# GyroAccelHeaders.net
KiCad netlist of a schematic drawn in Altium Designer
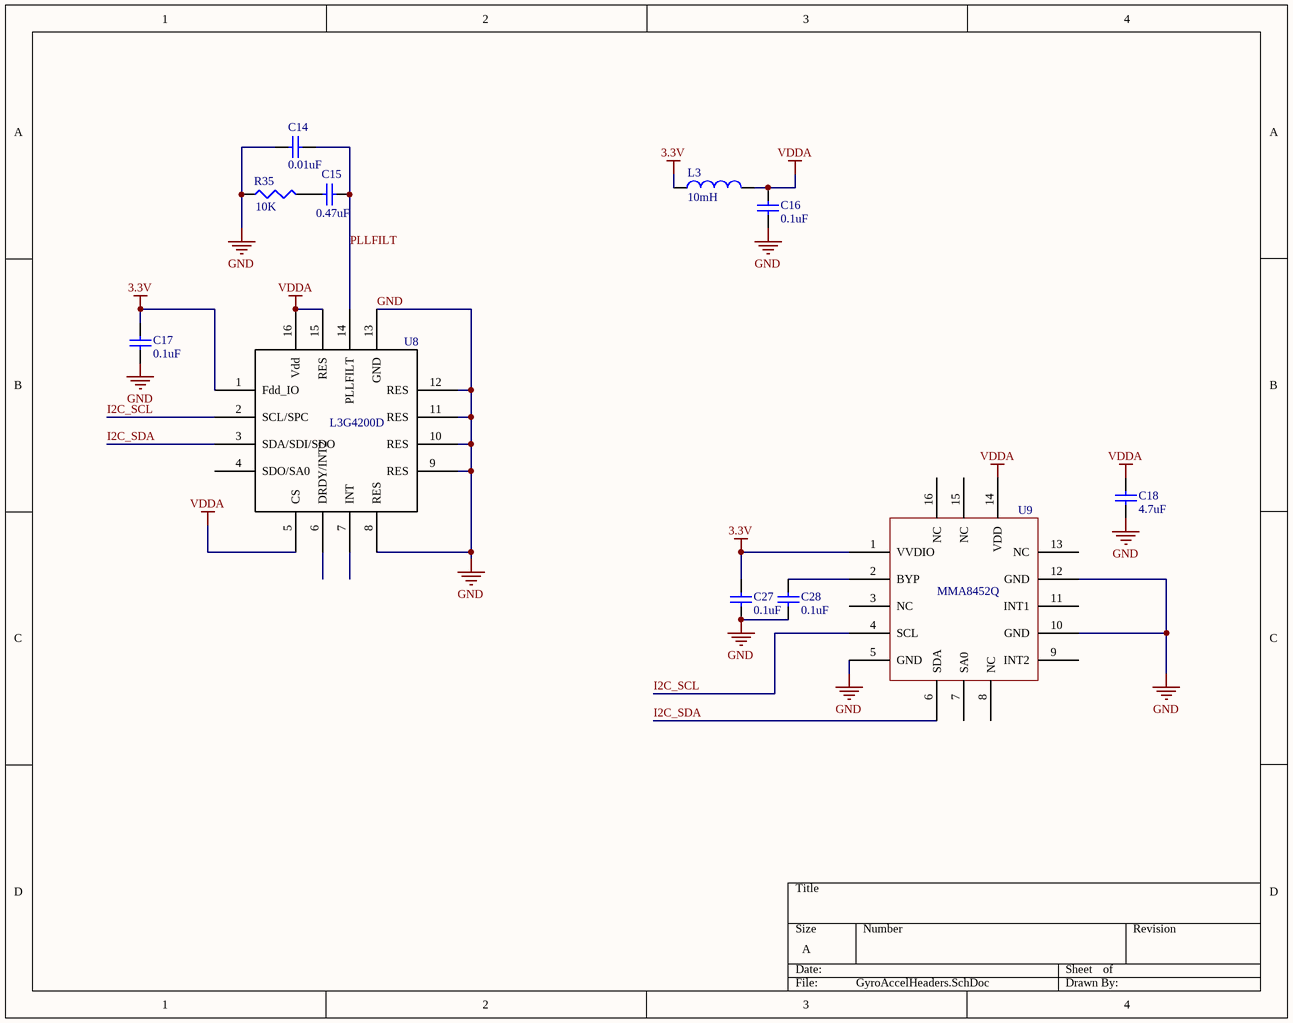
[diagram p0: GyroAccelHeaders.SchDoc]

(export (version "E")
  (design (tool "Eeschema 10.0.6"))
  (components
    (comp (ref "C14")
      (value "0.01uF")
      (footprint "CAPC1005L")
      (description "Capacitor (Semiconductor SIM Model)")
      (fields (field (name "Comment") "Cap Semi") (field (name "PUBLISHER") "Altium Limited"))
      (libsource (lib "Miscellaneous Devices") (part "Cap Semi"))
    )
    (comp (ref "C15")
      (value "0.47uF")
      (footprint "CAPC1005L")
      (description "Capacitor (Semiconductor SIM Model)")
      (fields (field (name "Comment") "Cap Semi") (field (name "PUBLISHER") "Altium Limited"))
      (libsource (lib "Miscellaneous Devices") (part "Cap Semi"))
    )
    (comp (ref "C16")
      (value "0.1uF")
      (footprint "CAPC1005L")
      (description "Capacitor (Semiconductor SIM Model)")
      (fields (field (name "Comment") "Cap Semi") (field (name "PUBLISHER") "Altium Limited"))
      (libsource (lib "Miscellaneous Devices") (part "Cap Semi"))
    )
    (comp (ref "C17")
      (value "0.1uF")
      (footprint "CAPC1005L")
      (description "Capacitor (Semiconductor SIM Model)")
      (fields (field (name "Comment") "Cap Semi") (field (name "PUBLISHER") "Altium Limited"))
      (libsource (lib "Miscellaneous Devices") (part "Cap Semi"))
    )
    (comp (ref "C18")
      (value "4.7uF")
      (footprint "CAPC1005L")
      (description "Capacitor (Semiconductor SIM Model)")
      (fields (field (name "Comment") "Cap Semi") (field (name "PUBLISHER") "Altium Limited"))
      (libsource (lib "Miscellaneous Devices") (part "Cap Semi"))
    )
    (comp (ref "C27")
      (value "0.1uF")
      (footprint "CAPC1005L")
      (description "Capacitor (Semiconductor SIM Model)")
      (fields (field (name "Comment") "Cap Semi") (field (name "PUBLISHER") "Altium Limited"))
      (libsource (lib "Miscellaneous Devices") (part "Cap Semi"))
    )
    (comp (ref "C28")
      (value "0.1uF")
      (footprint "CAPC1005L")
      (description "Capacitor (Semiconductor SIM Model)")
      (fields (field (name "Comment") "Cap Semi") (field (name "PUBLISHER") "Altium Limited"))
      (libsource (lib "Miscellaneous Devices") (part "Cap Semi"))
    )
    (comp (ref "L3")
      (value "10mH")
      (footprint "INDC2012L")
      (description "Inductor")
      (fields (field (name "PUBLISHER") "Altium Limited"))
      (libsource (lib "Miscellaneous Devices") (part "Inductor"))
    )
    (comp (ref "R35")
      (value "10K")
      (footprint "RESC1608L")
      (description "Resistor")
      (fields (field (name "Comment") "Res3") (field (name "PUBLISHER") "Altium Limited"))
      (libsource (lib "Miscellaneous Devices") (part "Res3"))
    )
    (comp (ref "U8")
      (value "L3G4200D")
      (footprint "L3G2004D")
      (description "3axis gyroscope, SPI")
      (libsource (lib "mrone") (part "L3G4200D"))
    )
    (comp (ref "U9") (value "MMA8452Q") (footprint "MMA8452Q") (libsource (lib "mrone") (part "MMA8452Q")))
  )
  (nets
    (net (code "1") (name "/I2C_SCL") (class "Default")
      (node (ref "U8") (pin "2") (pinfunction "SCL/SPC_2") (pintype "passive"))
      (node (ref "U9") (pin "4") (pinfunction "SCL_4") (pintype "passive"))
    )
    (net (code "2") (name "/I2C_SDA") (class "Default")
      (node (ref "U8") (pin "3") (pinfunction "SDA/SDI/SDO_3") (pintype "passive"))
      (node (ref "U9") (pin "6") (pinfunction "SDA_6") (pintype "passive"))
    )
    (net (code "3") (name "/PLLFILT") (class "Default")
      (node (ref "C14") (pin "1") (pinfunction "1_1") (pintype "passive"))
      (node (ref "C15") (pin "1") (pinfunction "1_1") (pintype "passive"))
      (node (ref "U8") (pin "14") (pinfunction "PLLFILT_14") (pintype "passive"))
    )
    (net (code "4") (name "3.3V") (class "Default")
      (node (ref "C17") (pin "2") (pinfunction "2_2") (pintype "passive"))
      (node (ref "C27") (pin "2") (pinfunction "2_2") (pintype "passive"))
      (node (ref "L3") (pin "2") (pinfunction "2_2") (pintype "passive"))
      (node (ref "U8") (pin "1") (pinfunction "Fdd_IO_1") (pintype "passive"))
      (node (ref "U9") (pin "1") (pinfunction "VVDIO_1") (pintype "passive"))
    )
    (net (code "5") (name "GND") (class "Default")
      (node (ref "C14") (pin "2") (pinfunction "2_2") (pintype "passive"))
      (node (ref "C16") (pin "1") (pinfunction "1_1") (pintype "passive"))
      (node (ref "C17") (pin "1") (pinfunction "1_1") (pintype "passive"))
      (node (ref "C18") (pin "1") (pinfunction "1_1") (pintype "passive"))
      (node (ref "C27") (pin "1") (pinfunction "1_1") (pintype "passive"))
      (node (ref "C28") (pin "1") (pinfunction "1_1") (pintype "passive"))
      (node (ref "R35") (pin "1") (pinfunction "1_1") (pintype "passive"))
      (node (ref "U8") (pin "10") (pinfunction "RES_10") (pintype "passive"))
      (node (ref "U8") (pin "11") (pinfunction "RES_11") (pintype "passive"))
      (node (ref "U8") (pin "12") (pinfunction "RES_12") (pintype "passive"))
      (node (ref "U8") (pin "13") (pinfunction "GND_13") (pintype "passive"))
      (node (ref "U8") (pin "8") (pinfunction "RES_8") (pintype "passive"))
      (node (ref "U8") (pin "9") (pinfunction "RES_9") (pintype "passive"))
      (node (ref "U9") (pin "10") (pinfunction "GND_10") (pintype "passive"))
      (node (ref "U9") (pin "12") (pinfunction "GND_12") (pintype "passive"))
      (node (ref "U9") (pin "5") (pinfunction "GND_5") (pintype "passive"))
    )
    (net (code "6") (name "Net-(C15-Pad2)") (class "Default")
      (node (ref "C15") (pin "2") (pinfunction "2_2") (pintype "passive"))
      (node (ref "R35") (pin "2") (pinfunction "2_2") (pintype "passive"))
    )
    (net (code "7") (name "Net-(U9-BYP)") (class "Default")
      (node (ref "C28") (pin "2") (pinfunction "2_2") (pintype "passive"))
      (node (ref "U9") (pin "2") (pinfunction "BYP_2") (pintype "passive"))
    )
    (net (code "8") (name "VDDA") (class "Default")
      (node (ref "C16") (pin "2") (pinfunction "2_2") (pintype "passive"))
      (node (ref "C18") (pin "2") (pinfunction "2_2") (pintype "passive"))
      (node (ref "L3") (pin "1") (pinfunction "1_1") (pintype "passive"))
      (node (ref "U8") (pin "15") (pinfunction "RES_15") (pintype "passive"))
      (node (ref "U8") (pin "16") (pinfunction "Vdd_16") (pintype "passive"))
      (node (ref "U8") (pin "5") (pinfunction "CS_5") (pintype "passive"))
      (node (ref "U9") (pin "14") (pinfunction "VDD_14") (pintype "passive"))
    )
    (net (code "9") (name "unconnected-(U8-DRDY{slash}INT2-Pad6)") (class "Default")
      (node (ref "U8") (pin "6") (pinfunction "DRDY/INT2_6") (pintype "passive"))
    )
    (net (code "10") (name "unconnected-(U8-INT-Pad7)") (class "Default")
      (node (ref "U8") (pin "7") (pinfunction "INT_7") (pintype "passive"))
    )
    (net (code "11") (name "unconnected-(U8-SDO{slash}SA0-Pad4)") (class "Default")
      (node (ref "U8") (pin "4") (pinfunction "SDO/SA0_4") (pintype "passive"))
    )
    (net (code "12") (name "unconnected-(U9-INT1-Pad11)") (class "Default")
      (node (ref "U9") (pin "11") (pinfunction "INT1_11") (pintype "passive"))
    )
    (net (code "13") (name "unconnected-(U9-INT2-Pad9)") (class "Default")
      (node (ref "U9") (pin "9") (pinfunction "INT2_9") (pintype "passive"))
    )
    (net (code "14") (name "unconnected-(U9-NC-Pad3)") (class "Default")
      (node (ref "U9") (pin "3") (pinfunction "NC_3") (pintype "passive"))
    )
    (net (code "15") (name "unconnected-(U9-NC-Pad8)") (class "Default")
      (node (ref "U9") (pin "8") (pinfunction "NC_8") (pintype "passive"))
    )
    (net (code "16") (name "unconnected-(U9-NC-Pad13)") (class "Default")
      (node (ref "U9") (pin "13") (pinfunction "NC_13") (pintype "passive"))
    )
    (net (code "17") (name "unconnected-(U9-NC-Pad15)") (class "Default")
      (node (ref "U9") (pin "15") (pinfunction "NC_15") (pintype "passive"))
    )
    (net (code "18") (name "unconnected-(U9-NC-Pad16)") (class "Default")
      (node (ref "U9") (pin "16") (pinfunction "NC_16") (pintype "passive"))
    )
    (net (code "19") (name "unconnected-(U9-SA0-Pad7)") (class "Default")
      (node (ref "U9") (pin "7") (pinfunction "SA0_7") (pintype "passive"))
    )
  )
)
